# Bank.net
KiCad netlist of a schematic drawn in Altium Designer
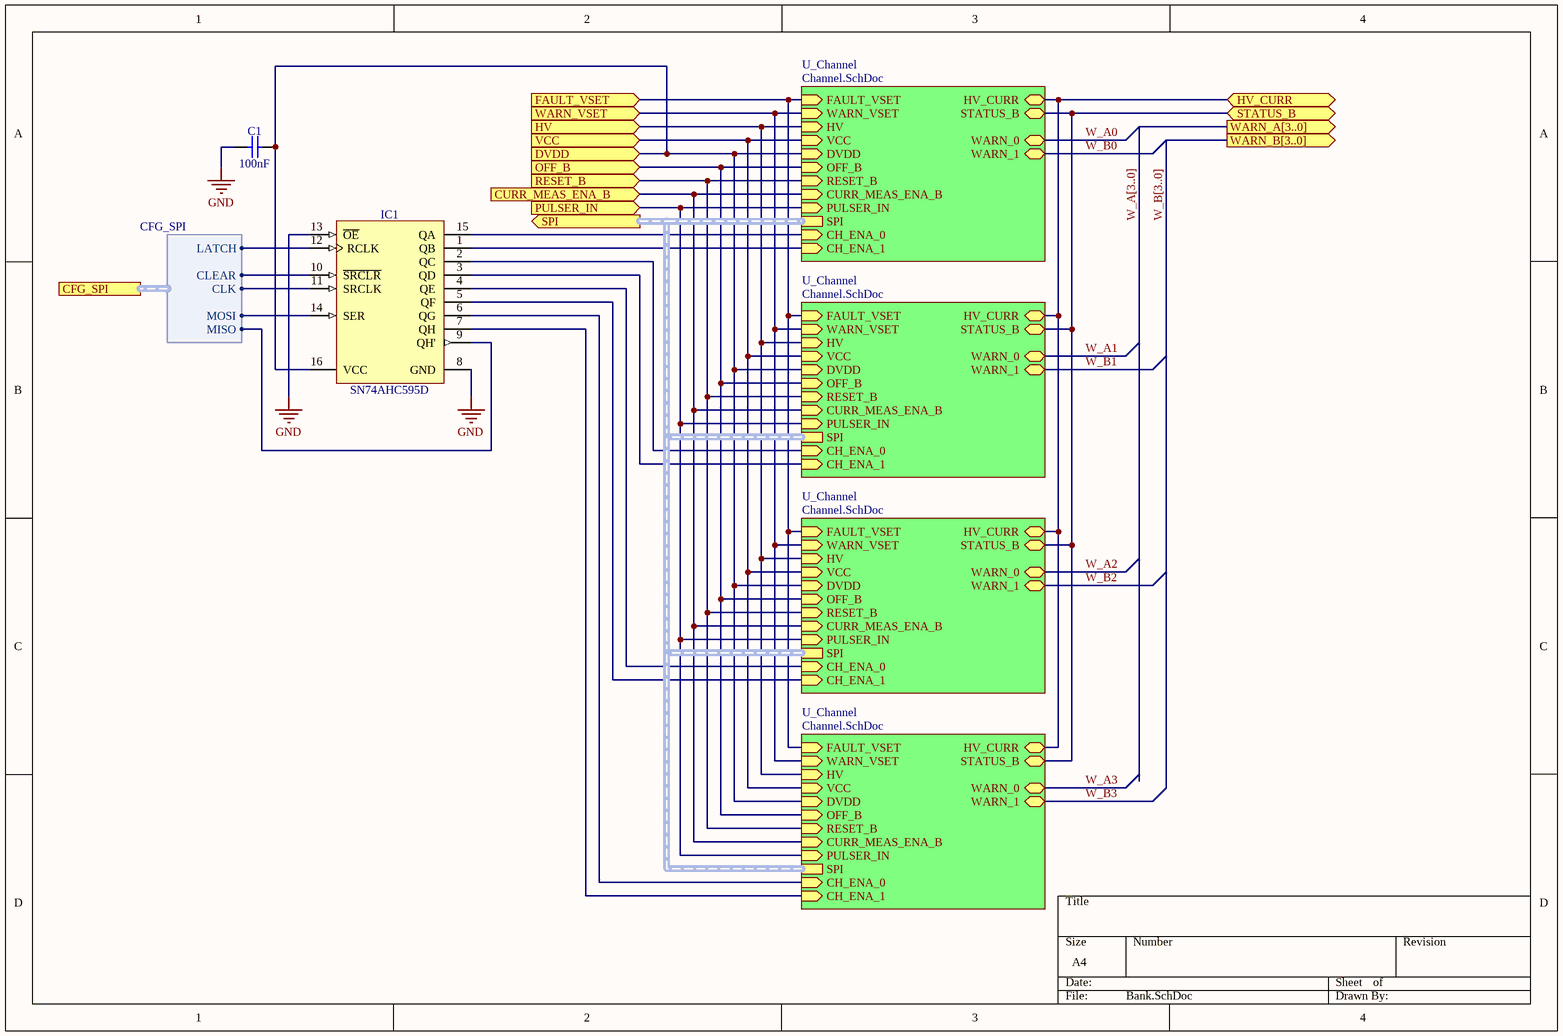
[diagram p0: Bank.SchDoc]

(export (version "E")
  (design (tool "Eeschema 10.0.6"))
  (components
    (comp (ref "C1")
      (value "100nF")
      (footprint "CAPC3216X140N")
      (description "Non-polarised capacitor")
      (fields
        (field (name "PART NUMBER") "CC1206_100NF_100V_10%_X7R")
        (field (name "VOLTAGE") "100V")
        (field (name "AUTHOR") "CERN DEM JLC")
      )
      (libsource (lib "Capacitors") (part "Capacitor - non polarized"))
    )
    (comp (ref "IC1")
      (value "SN74AHC595D")
      (footprint "SOIC127P600X175-16N")
      (description "8-Bit Shift Register With 3-State Output Register")
      (fields (field (name "MANUFACTURER") "TEXAS INSTRUMENTS") (field (name "AUTHOR") "CERN DEM JLC"))
      (libsource (lib "ICs And Semiconductors") (part "74595"))
    )
  )
  (nets
    (net (code "3") (name "/CH_ENA_0") (class "Default")
      (node (ref "IC1") (pin "15") (pinfunction "QA_15") (pintype "tri_state"))
    )
    (net (code "4") (name "/CH_ENA_0_1") (class "Default")
      (node (ref "IC1") (pin "4") (pinfunction "QE_4") (pintype "tri_state"))
    )
    (net (code "5") (name "/CH_ENA_0_2") (class "Default")
      (node (ref "IC1") (pin "6") (pinfunction "QG_6") (pintype "tri_state"))
    )
    (net (code "6") (name "/CH_ENA_0_3") (class "Default")
      (node (ref "IC1") (pin "2") (pinfunction "QC_2") (pintype "tri_state"))
    )
    (net (code "7") (name "/CH_ENA_1") (class "Default")
      (node (ref "IC1") (pin "3") (pinfunction "QD_3") (pintype "tri_state"))
    )
    (net (code "8") (name "/CH_ENA_1_1") (class "Default")
      (node (ref "IC1") (pin "5") (pinfunction "QF_5") (pintype "tri_state"))
    )
    (net (code "9") (name "/CH_ENA_1_2") (class "Default")
      (node (ref "IC1") (pin "7") (pinfunction "QH_7") (pintype "tri_state"))
    )
    (net (code "10") (name "/CH_ENA_1_3") (class "Default")
      (node (ref "IC1") (pin "1") (pinfunction "QB_1") (pintype "tri_state"))
    )
    (net (code "11") (name "/CLEAR") (class "Default")
      (node (ref "IC1") (pin "10") (pinfunction "~{SRCLR}_10") (pintype "input"))
    )
    (net (code "12") (name "/CLK") (class "Default")
      (node (ref "IC1") (pin "11") (pinfunction "SRCLK_11") (pintype "input"))
    )
    (net (code "14") (name "/DVDD") (class "Default")
      (node (ref "C1") (pin "2") (pinfunction "2_2") (pintype "passive"))
      (node (ref "IC1") (pin "16") (pinfunction "VCC_16") (pintype "power_in"))
    )
    (net (code "18") (name "/LATCH") (class "Default")
      (node (ref "IC1") (pin "12") (pinfunction "RCLK_12") (pintype "input"))
    )
    (net (code "19") (name "/MISO") (class "Default")
      (node (ref "IC1") (pin "9") (pinfunction "QH'_9") (pintype "output"))
    )
    (net (code "20") (name "/MOSI") (class "Default")
      (node (ref "IC1") (pin "14") (pinfunction "SER_14") (pintype "input"))
    )
    (net (code "39") (name "GND") (class "Default")
      (node (ref "C1") (pin "1") (pinfunction "1_1") (pintype "passive"))
      (node (ref "IC1") (pin "13") (pinfunction "~{OE}_13") (pintype "input"))
      (node (ref "IC1") (pin "8") (pinfunction "GND_8") (pintype "power_in"))
    )
  )
)
